# P_FET.net
KiCad netlist of a schematic drawn in Altium Designer
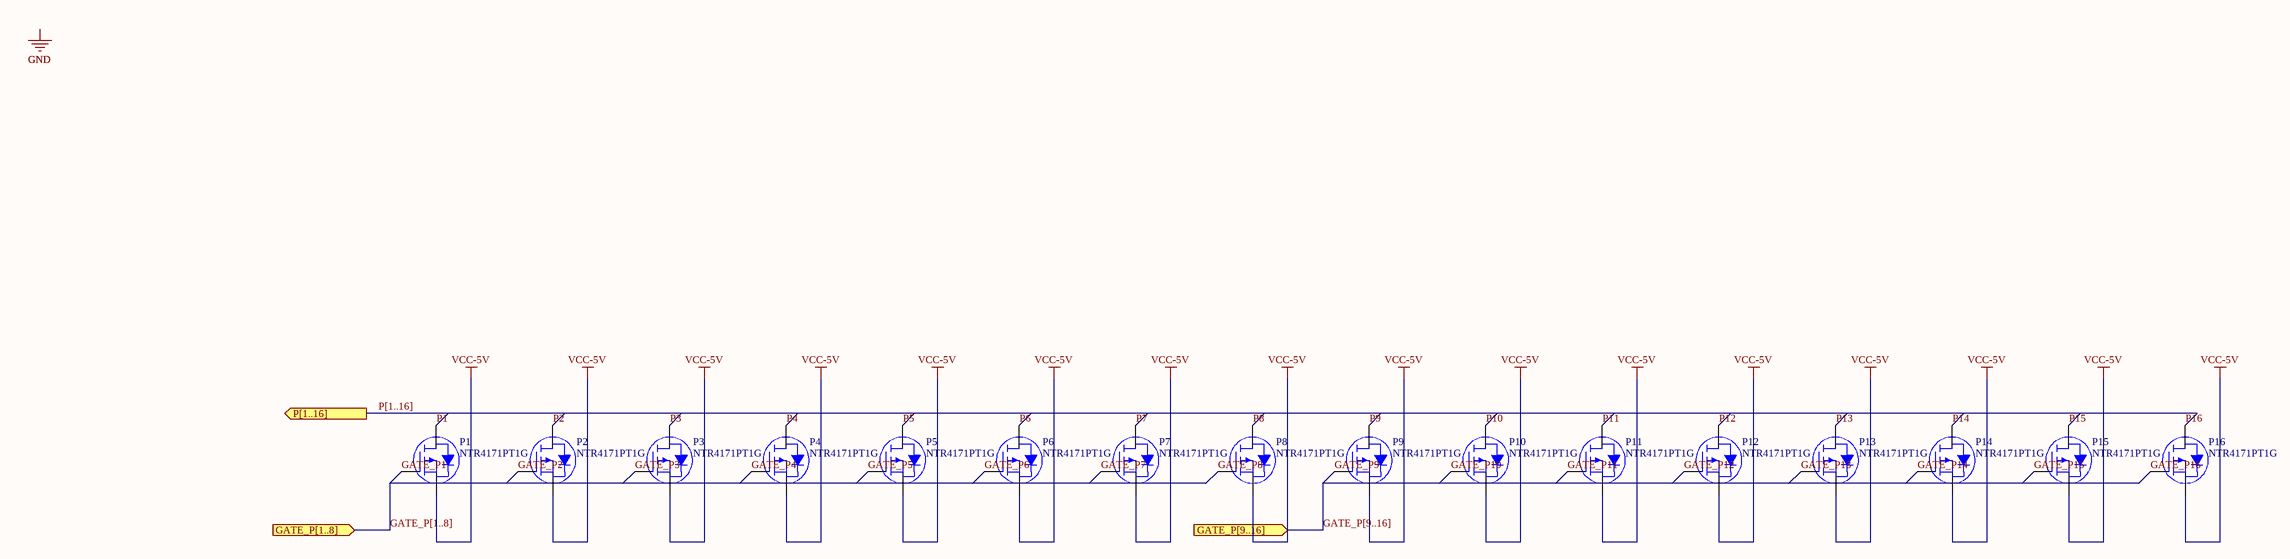
[diagram p0: P_FET.SchDoc]

(export (version "E")
  (design (tool "Eeschema 10.0.6"))
  (components
    (comp (ref "P1")
      (value "NTR4171PT1G")
      (footprint "ON SEMI SOT-23-3")
      (description "MOSFET P-CH 30V 2.2A SOT23")
      (fields (field (name "MANUFACTURER") "ON Semiconductor"))
      (libsource (lib "Celestial Library Database") (part "ON SEMI MOSFET P-CH SOT-23-3"))
    )
    (comp (ref "P2")
      (value "NTR4171PT1G")
      (footprint "ON SEMI SOT-23-3")
      (description "MOSFET P-CH 30V 2.2A SOT23")
      (fields (field (name "MANUFACTURER") "ON Semiconductor"))
      (libsource (lib "Celestial Library Database") (part "ON SEMI MOSFET P-CH SOT-23-3"))
    )
    (comp (ref "P3")
      (value "NTR4171PT1G")
      (footprint "ON SEMI SOT-23-3")
      (description "MOSFET P-CH 30V 2.2A SOT23")
      (fields (field (name "MANUFACTURER") "ON Semiconductor"))
      (libsource (lib "Celestial Library Database") (part "ON SEMI MOSFET P-CH SOT-23-3"))
    )
    (comp (ref "P4")
      (value "NTR4171PT1G")
      (footprint "ON SEMI SOT-23-3")
      (description "MOSFET P-CH 30V 2.2A SOT23")
      (fields (field (name "MANUFACTURER") "ON Semiconductor"))
      (libsource (lib "Celestial Library Database") (part "ON SEMI MOSFET P-CH SOT-23-3"))
    )
    (comp (ref "P5")
      (value "NTR4171PT1G")
      (footprint "ON SEMI SOT-23-3")
      (description "MOSFET P-CH 30V 2.2A SOT23")
      (fields (field (name "MANUFACTURER") "ON Semiconductor"))
      (libsource (lib "Celestial Library Database") (part "ON SEMI MOSFET P-CH SOT-23-3"))
    )
    (comp (ref "P6")
      (value "NTR4171PT1G")
      (footprint "ON SEMI SOT-23-3")
      (description "MOSFET P-CH 30V 2.2A SOT23")
      (fields (field (name "MANUFACTURER") "ON Semiconductor"))
      (libsource (lib "Celestial Library Database") (part "ON SEMI MOSFET P-CH SOT-23-3"))
    )
    (comp (ref "P7")
      (value "NTR4171PT1G")
      (footprint "ON SEMI SOT-23-3")
      (description "MOSFET P-CH 30V 2.2A SOT23")
      (fields (field (name "MANUFACTURER") "ON Semiconductor"))
      (libsource (lib "Celestial Library Database") (part "ON SEMI MOSFET P-CH SOT-23-3"))
    )
    (comp (ref "P8")
      (value "NTR4171PT1G")
      (footprint "ON SEMI SOT-23-3")
      (description "MOSFET P-CH 30V 2.2A SOT23")
      (fields (field (name "MANUFACTURER") "ON Semiconductor"))
      (libsource (lib "Celestial Library Database") (part "ON SEMI MOSFET P-CH SOT-23-3"))
    )
    (comp (ref "P9")
      (value "NTR4171PT1G")
      (footprint "ON SEMI SOT-23-3")
      (description "MOSFET P-CH 30V 2.2A SOT23")
      (fields (field (name "MANUFACTURER") "ON Semiconductor"))
      (libsource (lib "Celestial Library Database") (part "ON SEMI MOSFET P-CH SOT-23-3"))
    )
    (comp (ref "P10")
      (value "NTR4171PT1G")
      (footprint "ON SEMI SOT-23-3")
      (description "MOSFET P-CH 30V 2.2A SOT23")
      (fields (field (name "MANUFACTURER") "ON Semiconductor"))
      (libsource (lib "Celestial Library Database") (part "ON SEMI MOSFET P-CH SOT-23-3"))
    )
    (comp (ref "P11")
      (value "NTR4171PT1G")
      (footprint "ON SEMI SOT-23-3")
      (description "MOSFET P-CH 30V 2.2A SOT23")
      (fields (field (name "MANUFACTURER") "ON Semiconductor"))
      (libsource (lib "Celestial Library Database") (part "ON SEMI MOSFET P-CH SOT-23-3"))
    )
    (comp (ref "P12")
      (value "NTR4171PT1G")
      (footprint "ON SEMI SOT-23-3")
      (description "MOSFET P-CH 30V 2.2A SOT23")
      (fields (field (name "MANUFACTURER") "ON Semiconductor"))
      (libsource (lib "Celestial Library Database") (part "ON SEMI MOSFET P-CH SOT-23-3"))
    )
    (comp (ref "P13")
      (value "NTR4171PT1G")
      (footprint "ON SEMI SOT-23-3")
      (description "MOSFET P-CH 30V 2.2A SOT23")
      (fields (field (name "MANUFACTURER") "ON Semiconductor"))
      (libsource (lib "Celestial Library Database") (part "ON SEMI MOSFET P-CH SOT-23-3"))
    )
    (comp (ref "P14")
      (value "NTR4171PT1G")
      (footprint "ON SEMI SOT-23-3")
      (description "MOSFET P-CH 30V 2.2A SOT23")
      (fields (field (name "MANUFACTURER") "ON Semiconductor"))
      (libsource (lib "Celestial Library Database") (part "ON SEMI MOSFET P-CH SOT-23-3"))
    )
    (comp (ref "P15")
      (value "NTR4171PT1G")
      (footprint "ON SEMI SOT-23-3")
      (description "MOSFET P-CH 30V 2.2A SOT23")
      (fields (field (name "MANUFACTURER") "ON Semiconductor"))
      (libsource (lib "Celestial Library Database") (part "ON SEMI MOSFET P-CH SOT-23-3"))
    )
    (comp (ref "P16")
      (value "NTR4171PT1G")
      (footprint "ON SEMI SOT-23-3")
      (description "MOSFET P-CH 30V 2.2A SOT23")
      (fields (field (name "MANUFACTURER") "ON Semiconductor"))
      (libsource (lib "Celestial Library Database") (part "ON SEMI MOSFET P-CH SOT-23-3"))
    )
  )
  (nets
    (net (code "1") (name "/GATE_P1") (class "Default")
      (node (ref "P1") (pin "1") (pinfunction "G_1") (pintype "passive"))
    )
    (net (code "2") (name "/GATE_P2") (class "Default")
      (node (ref "P2") (pin "1") (pinfunction "G_1") (pintype "passive"))
    )
    (net (code "3") (name "/GATE_P3") (class "Default")
      (node (ref "P3") (pin "1") (pinfunction "G_1") (pintype "passive"))
    )
    (net (code "4") (name "/GATE_P4") (class "Default")
      (node (ref "P4") (pin "1") (pinfunction "G_1") (pintype "passive"))
    )
    (net (code "5") (name "/GATE_P5") (class "Default")
      (node (ref "P5") (pin "1") (pinfunction "G_1") (pintype "passive"))
    )
    (net (code "6") (name "/GATE_P6") (class "Default")
      (node (ref "P6") (pin "1") (pinfunction "G_1") (pintype "passive"))
    )
    (net (code "7") (name "/GATE_P7") (class "Default")
      (node (ref "P7") (pin "1") (pinfunction "G_1") (pintype "passive"))
    )
    (net (code "8") (name "/GATE_P8") (class "Default")
      (node (ref "P8") (pin "1") (pinfunction "G_1") (pintype "passive"))
    )
    (net (code "9") (name "/GATE_P9") (class "Default")
      (node (ref "P9") (pin "1") (pinfunction "G_1") (pintype "passive"))
    )
    (net (code "10") (name "/GATE_P10") (class "Default")
      (node (ref "P10") (pin "1") (pinfunction "G_1") (pintype "passive"))
    )
    (net (code "11") (name "/GATE_P11") (class "Default")
      (node (ref "P11") (pin "1") (pinfunction "G_1") (pintype "passive"))
    )
    (net (code "12") (name "/GATE_P12") (class "Default")
      (node (ref "P12") (pin "1") (pinfunction "G_1") (pintype "passive"))
    )
    (net (code "13") (name "/GATE_P13") (class "Default")
      (node (ref "P13") (pin "1") (pinfunction "G_1") (pintype "passive"))
    )
    (net (code "14") (name "/GATE_P14") (class "Default")
      (node (ref "P14") (pin "1") (pinfunction "G_1") (pintype "passive"))
    )
    (net (code "15") (name "/GATE_P15") (class "Default")
      (node (ref "P15") (pin "1") (pinfunction "G_1") (pintype "passive"))
    )
    (net (code "16") (name "/GATE_P16") (class "Default")
      (node (ref "P16") (pin "1") (pinfunction "G_1") (pintype "passive"))
    )
    (net (code "18") (name "/P1") (class "Default")
      (node (ref "P1") (pin "2") (pinfunction "D_2") (pintype "passive"))
    )
    (net (code "19") (name "/P2") (class "Default")
      (node (ref "P2") (pin "2") (pinfunction "D_2") (pintype "passive"))
    )
    (net (code "20") (name "/P3") (class "Default")
      (node (ref "P3") (pin "2") (pinfunction "D_2") (pintype "passive"))
    )
    (net (code "21") (name "/P4") (class "Default")
      (node (ref "P4") (pin "2") (pinfunction "D_2") (pintype "passive"))
    )
    (net (code "22") (name "/P5") (class "Default")
      (node (ref "P5") (pin "2") (pinfunction "D_2") (pintype "passive"))
    )
    (net (code "23") (name "/P6") (class "Default")
      (node (ref "P6") (pin "2") (pinfunction "D_2") (pintype "passive"))
    )
    (net (code "24") (name "/P7") (class "Default")
      (node (ref "P7") (pin "2") (pinfunction "D_2") (pintype "passive"))
    )
    (net (code "25") (name "/P8") (class "Default")
      (node (ref "P8") (pin "2") (pinfunction "D_2") (pintype "passive"))
    )
    (net (code "26") (name "/P9") (class "Default")
      (node (ref "P9") (pin "2") (pinfunction "D_2") (pintype "passive"))
    )
    (net (code "27") (name "/P10") (class "Default")
      (node (ref "P10") (pin "2") (pinfunction "D_2") (pintype "passive"))
    )
    (net (code "28") (name "/P11") (class "Default")
      (node (ref "P11") (pin "2") (pinfunction "D_2") (pintype "passive"))
    )
    (net (code "29") (name "/P12") (class "Default")
      (node (ref "P12") (pin "2") (pinfunction "D_2") (pintype "passive"))
    )
    (net (code "30") (name "/P13") (class "Default")
      (node (ref "P13") (pin "2") (pinfunction "D_2") (pintype "passive"))
    )
    (net (code "31") (name "/P14") (class "Default")
      (node (ref "P14") (pin "2") (pinfunction "D_2") (pintype "passive"))
    )
    (net (code "32") (name "/P15") (class "Default")
      (node (ref "P15") (pin "2") (pinfunction "D_2") (pintype "passive"))
    )
    (net (code "33") (name "/P16") (class "Default")
      (node (ref "P16") (pin "2") (pinfunction "D_2") (pintype "passive"))
    )
    (net (code "36") (name "VCC-5V") (class "Default")
      (node (ref "P1") (pin "3") (pinfunction "S_3") (pintype "passive"))
      (node (ref "P10") (pin "3") (pinfunction "S_3") (pintype "passive"))
      (node (ref "P11") (pin "3") (pinfunction "S_3") (pintype "passive"))
      (node (ref "P12") (pin "3") (pinfunction "S_3") (pintype "passive"))
      (node (ref "P13") (pin "3") (pinfunction "S_3") (pintype "passive"))
      (node (ref "P14") (pin "3") (pinfunction "S_3") (pintype "passive"))
      (node (ref "P15") (pin "3") (pinfunction "S_3") (pintype "passive"))
      (node (ref "P16") (pin "3") (pinfunction "S_3") (pintype "passive"))
      (node (ref "P2") (pin "3") (pinfunction "S_3") (pintype "passive"))
      (node (ref "P3") (pin "3") (pinfunction "S_3") (pintype "passive"))
      (node (ref "P4") (pin "3") (pinfunction "S_3") (pintype "passive"))
      (node (ref "P5") (pin "3") (pinfunction "S_3") (pintype "passive"))
      (node (ref "P6") (pin "3") (pinfunction "S_3") (pintype "passive"))
      (node (ref "P7") (pin "3") (pinfunction "S_3") (pintype "passive"))
      (node (ref "P8") (pin "3") (pinfunction "S_3") (pintype "passive"))
      (node (ref "P9") (pin "3") (pinfunction "S_3") (pintype "passive"))
    )
  )
)
